# apo_board_2014.net
KiCad netlist of a schematic drawn in EAGLE
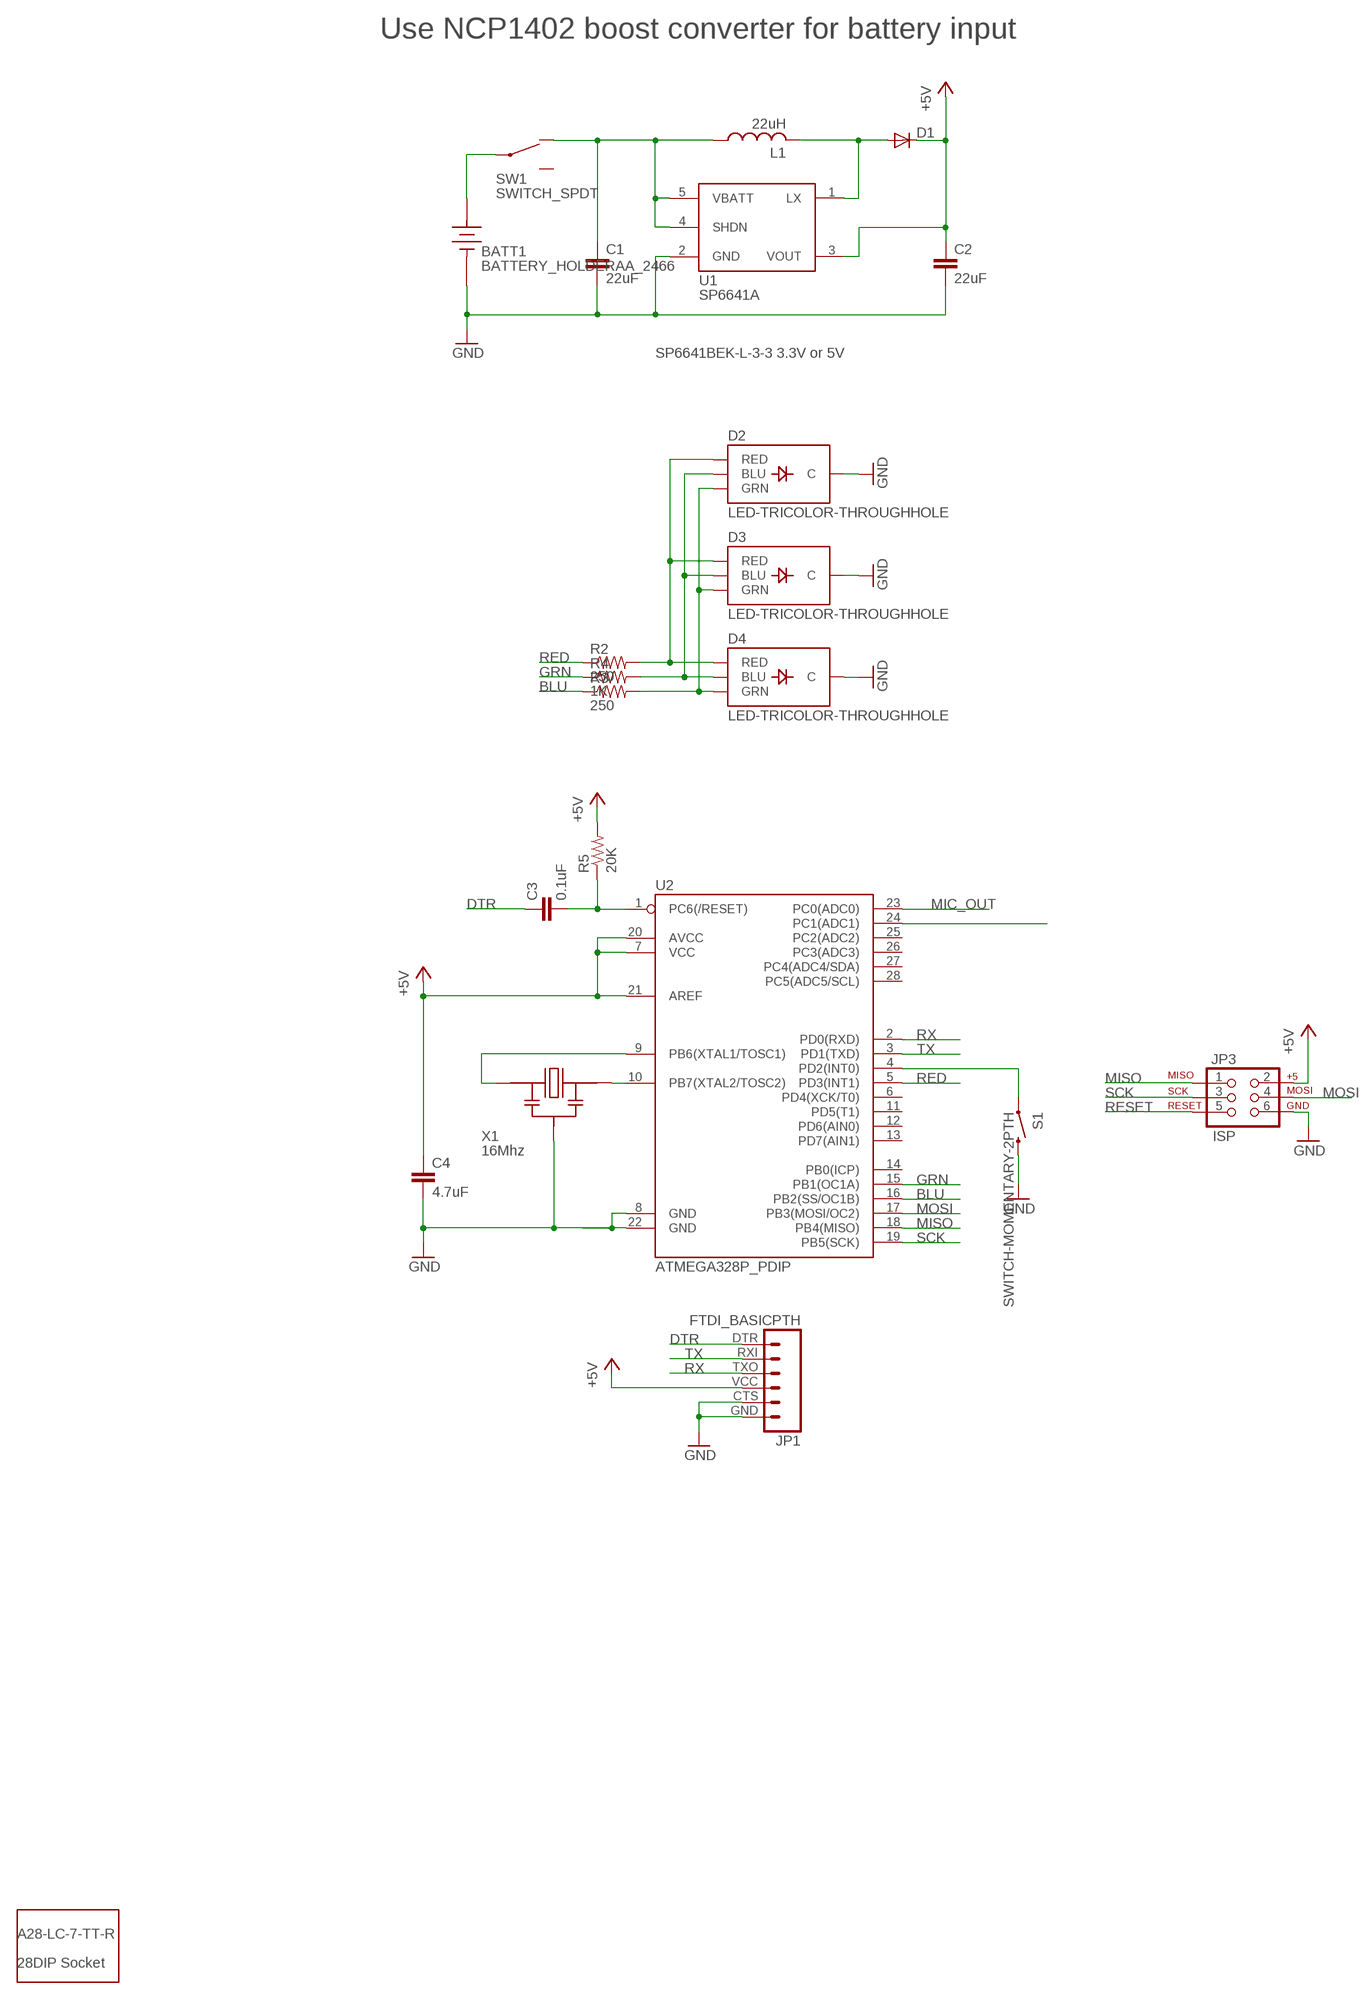
[diagram p0: schematic, sheet 1]

(export (version "E")
  (design (tool "Eeschema 10.0.6"))
  (components
    (comp (ref "BATT1")
      (value "BATTERY_HOLDERAA_2466")
      (footprint "eagle-import:BATT_HOLDER_AA_2466")
      (libsource (lib "eagle-import") (part "BATTERY_HOLDERAA_2466"))
    )
    (comp (ref "C1")
      (value "22uF")
      (footprint "eagle-import:CAP-PTH-SMALL-KIT")
      (libsource (lib "eagle-import") (part "CAPKIT"))
    )
    (comp (ref "C2")
      (value "22uF")
      (footprint "eagle-import:CAP-PTH-SMALL-KIT")
      (libsource (lib "eagle-import") (part "CAPKIT"))
    )
    (comp (ref "C3")
      (value "0.1uF")
      (footprint "eagle-import:CAP-PTH-SMALL-KIT")
      (libsource (lib "eagle-import") (part "CAPKIT"))
    )
    (comp (ref "C4")
      (value "4.7uF")
      (footprint "eagle-import:CAP-PTH-SMALL-KIT")
      (libsource (lib "eagle-import") (part "CAPKIT"))
    )
    (comp (ref "D1")
      (value "DIODEKIT")
      (footprint "eagle-import:DIODE-1N4148-KIT")
      (libsource (lib "eagle-import") (part "DIODEKIT"))
    )
    (comp (ref "D2")
      (value "LED-TRICOLOR-THROUGHHOLE")
      (footprint "eagle-import:LED-TRICOLOR-THROUGHHOLE")
      (libsource (lib "eagle-import") (part "LED-TRICOLOR-THROUGHHOLE"))
    )
    (comp (ref "D3")
      (value "LED-TRICOLOR-THROUGHHOLE")
      (footprint "eagle-import:LED-TRICOLOR-THROUGHHOLE")
      (libsource (lib "eagle-import") (part "LED-TRICOLOR-THROUGHHOLE"))
    )
    (comp (ref "D4")
      (value "LED-TRICOLOR-THROUGHHOLE")
      (footprint "eagle-import:LED-TRICOLOR-THROUGHHOLE")
      (libsource (lib "eagle-import") (part "LED-TRICOLOR-THROUGHHOLE"))
    )
    (comp (ref "JP1")
      (value "FTDI_BASICPTH")
      (footprint "eagle-import:FTDI_BASIC")
      (libsource (lib "eagle-import") (part "FTDI_BASICPTH"))
    )
    (comp (ref "JP3")
      (value "ISP")
      (footprint "eagle-import:2X3")
      (libsource (lib "eagle-import") (part "AVR_SPI_PRG_6PTH"))
    )
    (comp (ref "L1")
      (value "22uH")
      (footprint "eagle-import:INDUCTOR_AIUR-02H")
      (libsource (lib "eagle-import") (part "INDUCTORAIUR-02H"))
    )
    (comp (ref "R2")
      (value "250")
      (footprint "eagle-import:AXIAL-0.3-KIT")
      (libsource (lib "eagle-import") (part "RESISTORKIT"))
    )
    (comp (ref "R3")
      (value "250")
      (footprint "eagle-import:AXIAL-0.3-KIT")
      (libsource (lib "eagle-import") (part "RESISTORKIT"))
    )
    (comp (ref "R4")
      (value "1K")
      (footprint "eagle-import:AXIAL-0.3-KIT")
      (libsource (lib "eagle-import") (part "RESISTORKIT"))
    )
    (comp (ref "R5")
      (value "20K")
      (footprint "eagle-import:AXIAL-0.3-KIT")
      (libsource (lib "eagle-import") (part "RESISTORKIT"))
    )
    (comp (ref "S1")
      (value "SWITCH-MOMENTARY-2PTH")
      (footprint "eagle-import:TACTILE-PTH")
      (libsource (lib "eagle-import") (part "SWITCH-MOMENTARY-2PTH"))
    )
    (comp (ref "SW1")
      (value "SWITCH_SPDT")
      (footprint "eagle-import:SWITCH_SPDT_OS102011MA1QN1C")
      (libsource (lib "eagle-import") (part "SWITCH_SPDT"))
    )
    (comp (ref "U1")
      (value "SP6641A")
      (footprint "eagle-import:SOT23-5")
      (libsource (lib "eagle-import") (part "SP6641A"))
    )
    (comp (ref "U2")
      (value "ATMEGA328P_PDIP")
      (footprint "eagle-import:DIL28-3")
      (libsource (lib "eagle-import") (part "ATMEGA328P_PDIP"))
    )
    (comp (ref "X1")
      (value "16Mhz")
      (footprint "eagle-import:CERAMIC_RESONATOR_ZTT")
      (libsource (lib "eagle-import") (part "CERAMIC_RESONATOR"))
    )
  )
  (nets
    (net (code "1") (name "+5V") (class "Default")
      (node (ref "C2") (pin "1") (pinfunction "1_1") (pintype "passive"))
      (node (ref "C4") (pin "1") (pinfunction "1_1") (pintype "passive"))
      (node (ref "D1") (pin "C") (pinfunction "C_C") (pintype "passive"))
      (node (ref "JP1") (pin "VCC") (pinfunction "4_VCC") (pintype "passive"))
      (node (ref "JP3") (pin "2") (pinfunction "2_2") (pintype "passive"))
      (node (ref "R5") (pin "P$2") (pinfunction "2_P$2") (pintype "passive"))
      (node (ref "U1") (pin "3") (pinfunction "VOUT_3") (pintype "bidirectional"))
      (node (ref "U2") (pin "20") (pinfunction "AVCC_20") (pintype "bidirectional"))
      (node (ref "U2") (pin "21") (pinfunction "AREF_21") (pintype "bidirectional"))
      (node (ref "U2") (pin "7") (pinfunction "VCC_7") (pintype "bidirectional"))
    )
    (net (code "2") (name "/BLU") (class "Default")
      (node (ref "R3") (pin "P$1") (pinfunction "1_P$1") (pintype "passive"))
      (node (ref "U2") (pin "16") (pinfunction "PB2(SS/OC1B)_16") (pintype "bidirectional"))
    )
    (net (code "3") (name "/DTR") (class "Default")
      (node (ref "C3") (pin "1") (pinfunction "1_1") (pintype "passive"))
      (node (ref "JP1") (pin "DTR") (pinfunction "1_DTR") (pintype "passive"))
    )
    (net (code "4") (name "/GRN") (class "Default")
      (node (ref "R4") (pin "P$1") (pinfunction "1_P$1") (pintype "passive"))
      (node (ref "U2") (pin "15") (pinfunction "PB1(OC1A)_15") (pintype "bidirectional"))
    )
    (net (code "5") (name "/MIC_OUT") (class "Default")
      (node (ref "U2") (pin "23") (pinfunction "PC0(ADC0)_23") (pintype "bidirectional"))
    )
    (net (code "6") (name "/MISO") (class "Default")
      (node (ref "JP3") (pin "1") (pinfunction "1_1") (pintype "passive"))
      (node (ref "U2") (pin "18") (pinfunction "PB4(MISO)_18") (pintype "bidirectional"))
    )
    (net (code "7") (name "/MOSI") (class "Default")
      (node (ref "JP3") (pin "4") (pinfunction "4_4") (pintype "passive"))
      (node (ref "U2") (pin "17") (pinfunction "PB3(MOSI/OC2)_17") (pintype "bidirectional"))
    )
    (net (code "8") (name "/RED") (class "Default")
      (node (ref "R2") (pin "P$1") (pinfunction "1_P$1") (pintype "passive"))
      (node (ref "U2") (pin "5") (pinfunction "PD3(INT1)_5") (pintype "bidirectional"))
    )
    (net (code "9") (name "/RESET") (class "Default")
      (node (ref "JP3") (pin "5") (pinfunction "5_5") (pintype "passive"))
    )
    (net (code "10") (name "/RX") (class "Default")
      (node (ref "JP1") (pin "TXO") (pinfunction "3_TXO") (pintype "passive"))
      (node (ref "U2") (pin "2") (pinfunction "PD0(RXD)_2") (pintype "bidirectional"))
    )
    (net (code "11") (name "/SCK") (class "Default")
      (node (ref "JP3") (pin "3") (pinfunction "3_3") (pintype "passive"))
      (node (ref "U2") (pin "19") (pinfunction "PB5(SCK)_19") (pintype "bidirectional"))
    )
    (net (code "12") (name "/TX") (class "Default")
      (node (ref "JP1") (pin "RXI") (pinfunction "2_RXI") (pintype "passive"))
      (node (ref "U2") (pin "3") (pinfunction "PD1(TXD)_3") (pintype "bidirectional"))
    )
    (net (code "13") (name "GND") (class "Default")
      (node (ref "BATT1") (pin "N") (pinfunction "N_N") (pintype "bidirectional"))
      (node (ref "C1") (pin "2") (pinfunction "2_2") (pintype "passive"))
      (node (ref "C2") (pin "2") (pinfunction "2_2") (pintype "passive"))
      (node (ref "C4") (pin "2") (pinfunction "2_2") (pintype "passive"))
      (node (ref "D2") (pin "GND") (pinfunction "C_GND") (pintype "bidirectional"))
      (node (ref "D3") (pin "GND") (pinfunction "C_GND") (pintype "bidirectional"))
      (node (ref "D4") (pin "GND") (pinfunction "C_GND") (pintype "bidirectional"))
      (node (ref "JP1") (pin "CTS") (pinfunction "5_CTS") (pintype "passive"))
      (node (ref "JP1") (pin "GND") (pinfunction "6_GND") (pintype "passive"))
      (node (ref "JP3") (pin "6") (pinfunction "6_6") (pintype "passive"))
      (node (ref "S1") (pin "3") (pinfunction "2_3") (pintype "passive"))
      (node (ref "U1") (pin "2") (pinfunction "GND_2") (pintype "bidirectional"))
      (node (ref "U2") (pin "22") (pinfunction "GND_22") (pintype "bidirectional"))
      (node (ref "U2") (pin "8") (pinfunction "GND_8") (pintype "bidirectional"))
      (node (ref "X1") (pin "P$2") (pinfunction "P$2_P$2") (pintype "bidirectional"))
    )
    (net (code "14") (name "Net-(L1-1)") (class "Default")
      (node (ref "C1") (pin "1") (pinfunction "1_1") (pintype "passive"))
      (node (ref "L1") (pin "P$1") (pinfunction "1_P$1") (pintype "passive"))
      (node (ref "SW1") (pin "P$3") (pinfunction "3_P$3") (pintype "passive"))
      (node (ref "U1") (pin "4") (pinfunction "SHDN_4") (pintype "bidirectional"))
      (node (ref "U1") (pin "5") (pinfunction "VBATT_5") (pintype "bidirectional"))
    )
    (net (code "15") (name "Net-(L1-2)") (class "Default")
      (node (ref "D1") (pin "A") (pinfunction "A_A") (pintype "passive"))
      (node (ref "L1") (pin "P$2") (pinfunction "2_P$2") (pintype "passive"))
      (node (ref "U1") (pin "1") (pinfunction "LX_1") (pintype "bidirectional"))
    )
    (net (code "16") (name "Net-(R2-2)") (class "Default")
      (node (ref "D2") (pin "RED") (pinfunction "RED_RED") (pintype "bidirectional"))
      (node (ref "D3") (pin "RED") (pinfunction "RED_RED") (pintype "bidirectional"))
      (node (ref "D4") (pin "RED") (pinfunction "RED_RED") (pintype "bidirectional"))
      (node (ref "R2") (pin "P$2") (pinfunction "2_P$2") (pintype "passive"))
    )
    (net (code "17") (name "Net-(R3-2)") (class "Default")
      (node (ref "D2") (pin "GRN") (pinfunction "GRN_GRN") (pintype "bidirectional"))
      (node (ref "D3") (pin "GRN") (pinfunction "GRN_GRN") (pintype "bidirectional"))
      (node (ref "D4") (pin "GRN") (pinfunction "GRN_GRN") (pintype "bidirectional"))
      (node (ref "R3") (pin "P$2") (pinfunction "2_P$2") (pintype "passive"))
    )
    (net (code "18") (name "Net-(R4-2)") (class "Default")
      (node (ref "D2") (pin "BLU") (pinfunction "BLU_BLU") (pintype "bidirectional"))
      (node (ref "D3") (pin "BLU") (pinfunction "BLU_BLU") (pintype "bidirectional"))
      (node (ref "D4") (pin "BLU") (pinfunction "BLU_BLU") (pintype "bidirectional"))
      (node (ref "R4") (pin "P$2") (pinfunction "2_P$2") (pintype "passive"))
    )
    (net (code "19") (name "Net-(R5-1)") (class "Default")
      (node (ref "C3") (pin "2") (pinfunction "2_2") (pintype "passive"))
      (node (ref "R5") (pin "P$1") (pinfunction "1_P$1") (pintype "passive"))
      (node (ref "U2") (pin "1") (pinfunction "PC6(/RESET)_1") (pintype "bidirectional"))
    )
    (net (code "20") (name "Net-(SW1-COMMON)") (class "Default")
      (node (ref "BATT1") (pin "P") (pinfunction "P_P") (pintype "bidirectional"))
      (node (ref "SW1") (pin "P$2") (pinfunction "COMMON_P$2") (pintype "passive"))
    )
    (net (code "21") (name "Net-(U2-PB6(XTAL1{slash}TOSC1))") (class "Default")
      (node (ref "U2") (pin "9") (pinfunction "PB6(XTAL1/TOSC1)_9") (pintype "bidirectional"))
      (node (ref "X1") (pin "P$1") (pinfunction "P$1_P$1") (pintype "bidirectional"))
    )
    (net (code "22") (name "Net-(U2-PB7(XTAL2{slash}TOSC2))") (class "Default")
      (node (ref "U2") (pin "10") (pinfunction "PB7(XTAL2/TOSC2)_10") (pintype "bidirectional"))
      (node (ref "X1") (pin "P$3") (pinfunction "P$3_P$3") (pintype "bidirectional"))
    )
    (net (code "23") (name "Net-(U2-PD2(INT0))") (class "Default")
      (node (ref "S1") (pin "1") (pinfunction "1_1") (pintype "passive"))
      (node (ref "U2") (pin "4") (pinfunction "PD2(INT0)_4") (pintype "bidirectional"))
    )
    (net (code "24") (name "unconnected-(SW1-2-PadP$1)") (class "Default")
      (node (ref "SW1") (pin "P$1") (pinfunction "2_P$1") (pintype "passive"))
    )
    (net (code "25") (name "unconnected-(U2-PB0(ICP)-Pad14)") (class "Default")
      (node (ref "U2") (pin "14") (pinfunction "PB0(ICP)_14") (pintype "bidirectional"))
    )
    (net (code "26") (name "unconnected-(U2-PC1(ADC1)-Pad24)") (class "Default")
      (node (ref "U2") (pin "24") (pinfunction "PC1(ADC1)_24") (pintype "bidirectional"))
    )
    (net (code "27") (name "unconnected-(U2-PC2(ADC2)-Pad25)") (class "Default")
      (node (ref "U2") (pin "25") (pinfunction "PC2(ADC2)_25") (pintype "bidirectional"))
    )
    (net (code "28") (name "unconnected-(U2-PC3(ADC3)-Pad26)") (class "Default")
      (node (ref "U2") (pin "26") (pinfunction "PC3(ADC3)_26") (pintype "bidirectional"))
    )
    (net (code "29") (name "unconnected-(U2-PC4(ADC4{slash}SDA)-Pad27)") (class "Default")
      (node (ref "U2") (pin "27") (pinfunction "PC4(ADC4/SDA)_27") (pintype "bidirectional"))
    )
    (net (code "30") (name "unconnected-(U2-PC5(ADC5{slash}SCL)-Pad28)") (class "Default")
      (node (ref "U2") (pin "28") (pinfunction "PC5(ADC5/SCL)_28") (pintype "bidirectional"))
    )
    (net (code "31") (name "unconnected-(U2-PD4(XCK{slash}T0)-Pad6)") (class "Default")
      (node (ref "U2") (pin "6") (pinfunction "PD4(XCK/T0)_6") (pintype "bidirectional"))
    )
    (net (code "32") (name "unconnected-(U2-PD5(T1)-Pad11)") (class "Default")
      (node (ref "U2") (pin "11") (pinfunction "PD5(T1)_11") (pintype "bidirectional"))
    )
    (net (code "33") (name "unconnected-(U2-PD6(AIN0)-Pad12)") (class "Default")
      (node (ref "U2") (pin "12") (pinfunction "PD6(AIN0)_12") (pintype "bidirectional"))
    )
    (net (code "34") (name "unconnected-(U2-PD7(AIN1)-Pad13)") (class "Default")
      (node (ref "U2") (pin "13") (pinfunction "PD7(AIN1)_13") (pintype "bidirectional"))
    )
  )
)
